# Backplane-Connector.net
KiCad netlist of a schematic drawn in Altium Designer
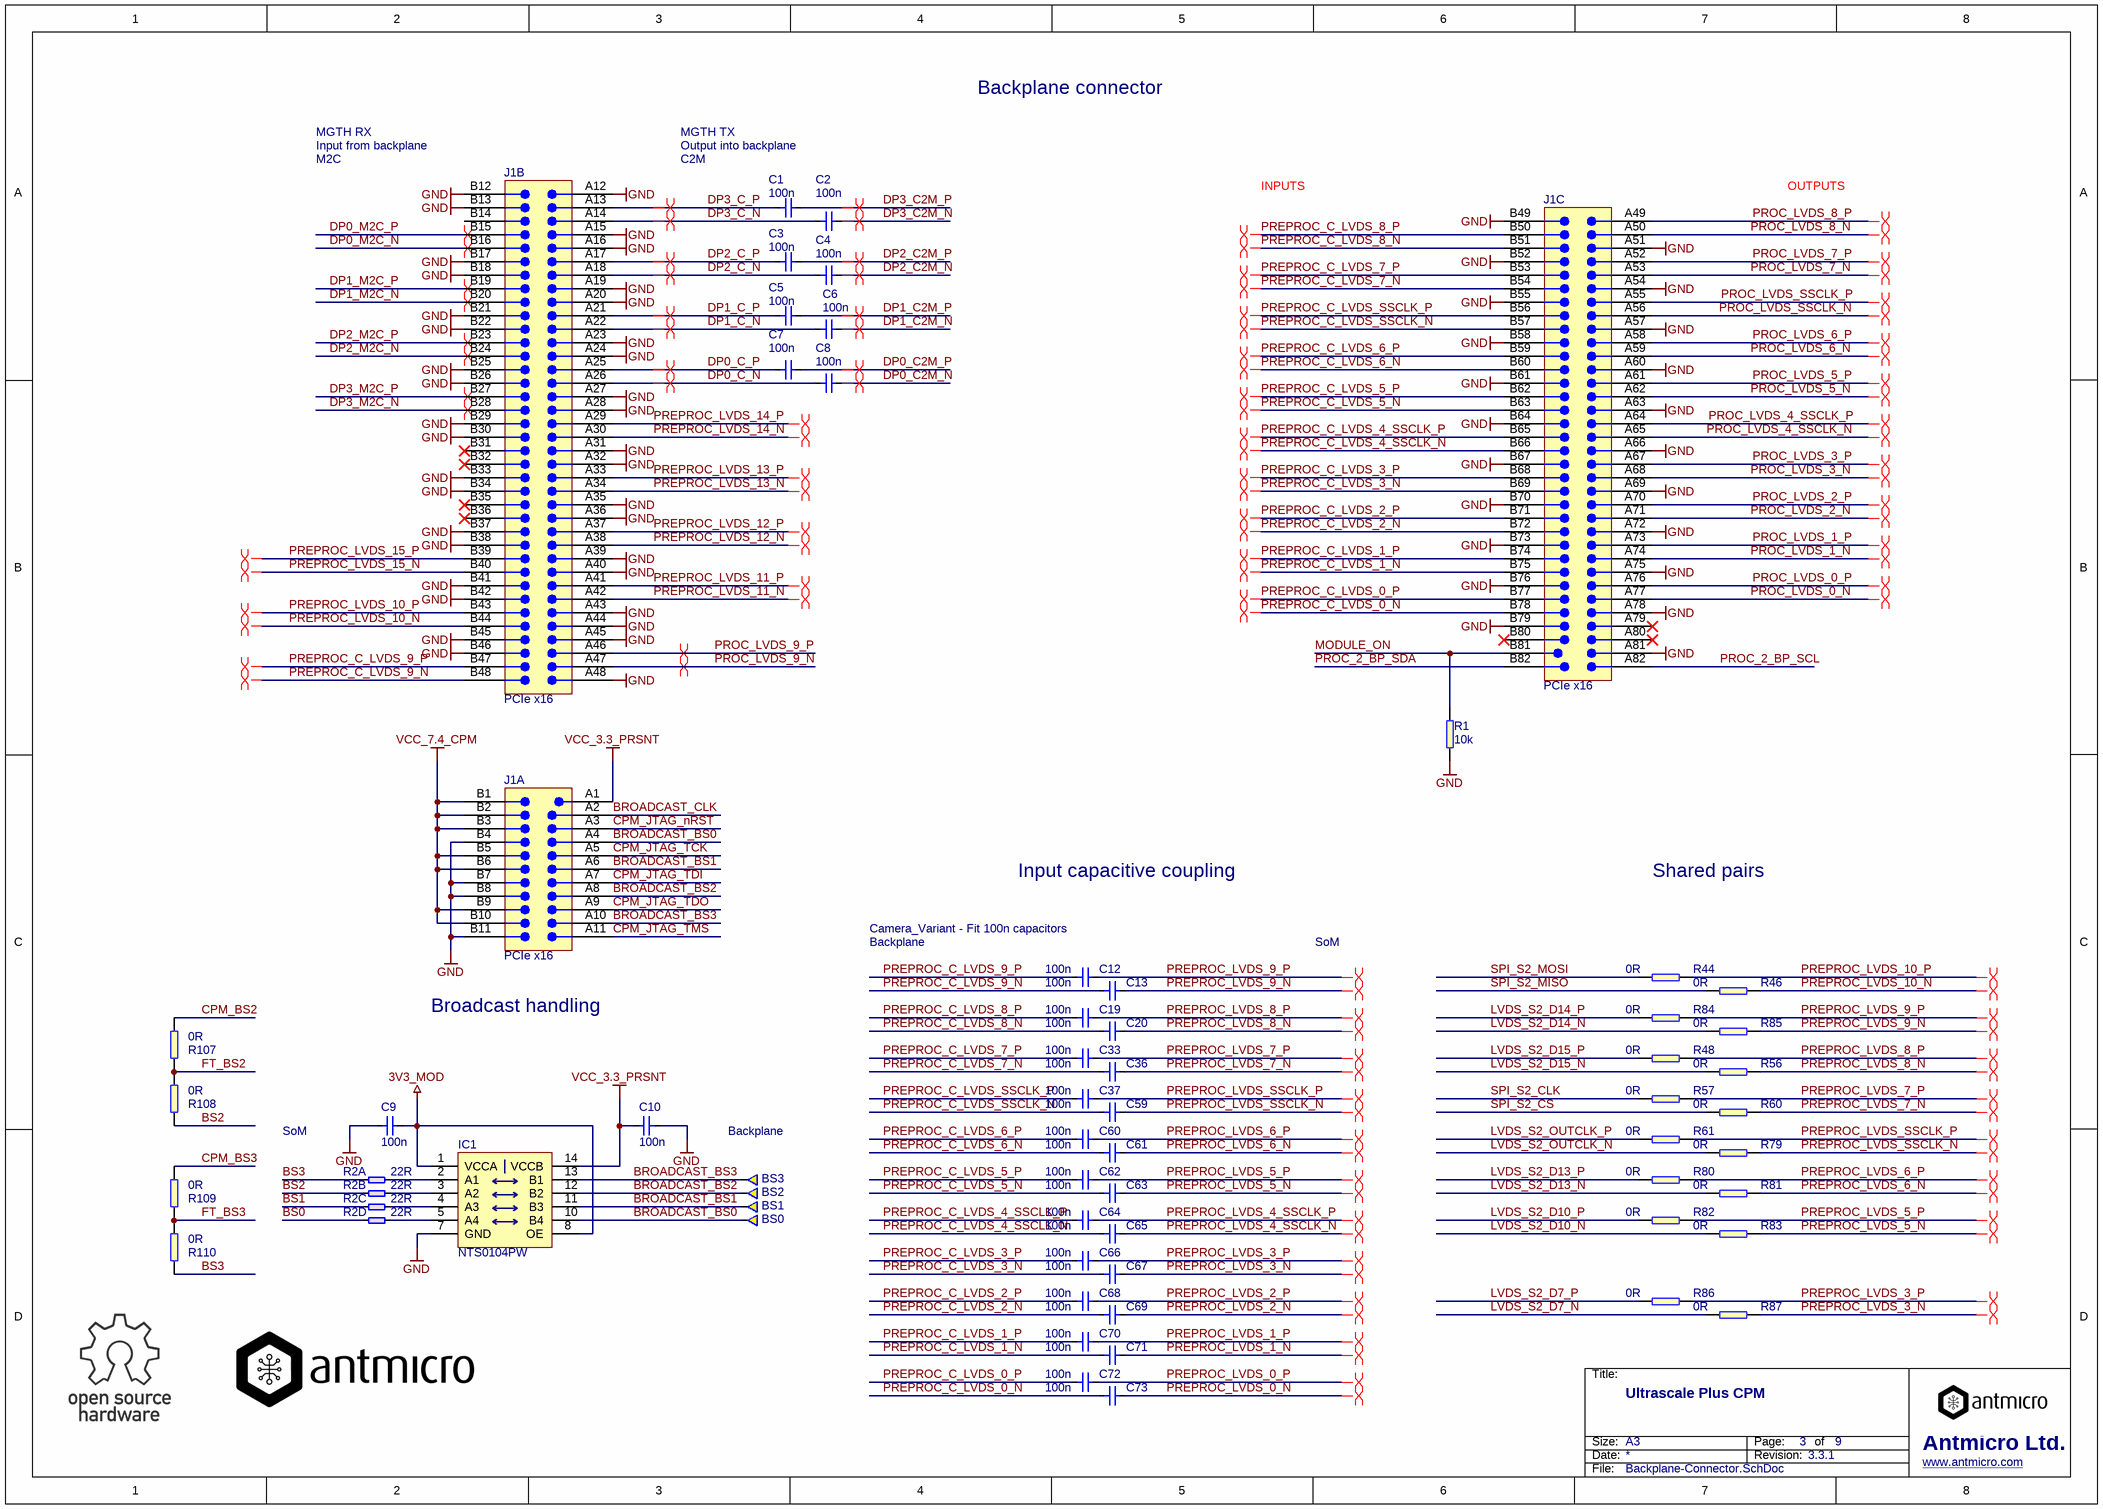
[diagram p0: Backplane-Connector.SchDoc]

(export (version "E")
  (design (tool "Eeschema 10.0.6"))
  (components
    (comp (ref "BS0")
      (value "*")
      (footprint "Testpad")
      (description "Testpad 2mm diameter")
      (fields (field (name "PART NUMBER") "Testpad"))
      (libsource (lib "US-Plus-CPM") (part "Testpad"))
    )
    (comp (ref "BS1")
      (value "*")
      (footprint "Testpad")
      (description "Testpad 2mm diameter")
      (fields (field (name "PART NUMBER") "Testpad"))
      (libsource (lib "US-Plus-CPM") (part "Testpad"))
    )
    (comp (ref "BS2")
      (value "*")
      (footprint "Testpad")
      (description "Testpad 2mm diameter")
      (fields (field (name "PART NUMBER") "Testpad"))
      (libsource (lib "US-Plus-CPM") (part "Testpad"))
    )
    (comp (ref "BS3")
      (value "*")
      (footprint "Testpad")
      (description "Testpad 2mm diameter")
      (fields (field (name "PART NUMBER") "Testpad"))
      (libsource (lib "US-Plus-CPM") (part "Testpad"))
    )
    (comp (ref "C1")
      (value "100n")
      (footprint "0402")
      (description "MLCC SMT Capacitor 100nF 0402")
      (fields (field (name "PART NUMBER") "C_100n_0402") (field (name "MANUFACTURER") "MULTICOMP"))
      (libsource (lib "US-Plus-CPM") (part "C"))
    )
    (comp (ref "C2")
      (value "100n")
      (footprint "0402")
      (description "MLCC SMT Capacitor 100nF 0402")
      (fields (field (name "PART NUMBER") "C_100n_0402") (field (name "MANUFACTURER") "MULTICOMP"))
      (libsource (lib "US-Plus-CPM") (part "C"))
    )
    (comp (ref "C3")
      (value "100n")
      (footprint "0402")
      (description "MLCC SMT Capacitor 100nF 0402")
      (fields (field (name "PART NUMBER") "C_100n_0402") (field (name "MANUFACTURER") "MULTICOMP"))
      (libsource (lib "US-Plus-CPM") (part "C"))
    )
    (comp (ref "C4")
      (value "100n")
      (footprint "0402")
      (description "MLCC SMT Capacitor 100nF 0402")
      (fields (field (name "PART NUMBER") "C_100n_0402") (field (name "MANUFACTURER") "MULTICOMP"))
      (libsource (lib "US-Plus-CPM") (part "C"))
    )
    (comp (ref "C5")
      (value "100n")
      (footprint "0402")
      (description "MLCC SMT Capacitor 100nF 0402")
      (fields (field (name "PART NUMBER") "C_100n_0402") (field (name "MANUFACTURER") "MULTICOMP"))
      (libsource (lib "US-Plus-CPM") (part "C"))
    )
    (comp (ref "C6")
      (value "100n")
      (footprint "0402")
      (description "MLCC SMT Capacitor 100nF 0402")
      (fields (field (name "PART NUMBER") "C_100n_0402") (field (name "MANUFACTURER") "MULTICOMP"))
      (libsource (lib "US-Plus-CPM") (part "C"))
    )
    (comp (ref "C7")
      (value "100n")
      (footprint "0402")
      (description "MLCC SMT Capacitor 100nF 0402")
      (fields (field (name "PART NUMBER") "C_100n_0402") (field (name "MANUFACTURER") "MULTICOMP"))
      (libsource (lib "US-Plus-CPM") (part "C"))
    )
    (comp (ref "C8")
      (value "100n")
      (footprint "0402")
      (description "MLCC SMT Capacitor 100nF 0402")
      (fields (field (name "PART NUMBER") "C_100n_0402") (field (name "MANUFACTURER") "MULTICOMP"))
      (libsource (lib "US-Plus-CPM") (part "C"))
    )
    (comp (ref "C9")
      (value "100n")
      (footprint "0402")
      (description "MLCC SMT Capacitor 100nF 0402")
      (fields (field (name "PART NUMBER") "C_100n_0402") (field (name "MANUFACTURER") "MULTICOMP"))
      (libsource (lib "US-Plus-CPM") (part "C"))
    )
    (comp (ref "C10")
      (value "100n")
      (footprint "0402")
      (description "MLCC SMT Capacitor 100nF 0402")
      (fields (field (name "PART NUMBER") "C_100n_0402") (field (name "MANUFACTURER") "MULTICOMP"))
      (libsource (lib "US-Plus-CPM") (part "C"))
    )
    (comp (ref "C12")
      (value "100n")
      (footprint "0402")
      (description "MLCC SMT Capacitor 100nF 0402")
      (fields (field (name "PART NUMBER") "C_100n_0402") (field (name "MANUFACTURER") "MULTICOMP"))
      (libsource (lib "US-Plus-CPM") (part "C"))
    )
    (comp (ref "C13")
      (value "100n")
      (footprint "0402")
      (description "MLCC SMT Capacitor 100nF 0402")
      (fields (field (name "PART NUMBER") "C_100n_0402") (field (name "MANUFACTURER") "MULTICOMP"))
      (libsource (lib "US-Plus-CPM") (part "C"))
    )
    (comp (ref "C19")
      (value "100n")
      (footprint "0402")
      (description "MLCC SMT Capacitor 100nF 0402")
      (fields (field (name "PART NUMBER") "C_100n_0402") (field (name "MANUFACTURER") "MULTICOMP"))
      (libsource (lib "US-Plus-CPM") (part "C"))
    )
    (comp (ref "C20")
      (value "100n")
      (footprint "0402")
      (description "MLCC SMT Capacitor 100nF 0402")
      (fields (field (name "PART NUMBER") "C_100n_0402") (field (name "MANUFACTURER") "MULTICOMP"))
      (libsource (lib "US-Plus-CPM") (part "C"))
    )
    (comp (ref "C33")
      (value "100n")
      (footprint "0402")
      (description "MLCC SMT Capacitor 100nF 0402")
      (fields (field (name "PART NUMBER") "C_100n_0402") (field (name "MANUFACTURER") "MULTICOMP"))
      (libsource (lib "US-Plus-CPM") (part "C"))
    )
    (comp (ref "C36")
      (value "100n")
      (footprint "0402")
      (description "MLCC SMT Capacitor 100nF 0402")
      (fields (field (name "PART NUMBER") "C_100n_0402") (field (name "MANUFACTURER") "MULTICOMP"))
      (libsource (lib "US-Plus-CPM") (part "C"))
    )
    (comp (ref "C37")
      (value "100n")
      (footprint "0402")
      (description "MLCC SMT Capacitor 100nF 0402")
      (fields (field (name "PART NUMBER") "C_100n_0402") (field (name "MANUFACTURER") "MULTICOMP"))
      (libsource (lib "US-Plus-CPM") (part "C"))
    )
    (comp (ref "C59")
      (value "100n")
      (footprint "0402")
      (description "MLCC SMT Capacitor 100nF 0402")
      (fields (field (name "PART NUMBER") "C_100n_0402") (field (name "MANUFACTURER") "MULTICOMP"))
      (libsource (lib "US-Plus-CPM") (part "C"))
    )
    (comp (ref "C60")
      (value "100n")
      (footprint "0402")
      (description "MLCC SMT Capacitor 100nF 0402")
      (fields (field (name "PART NUMBER") "C_100n_0402") (field (name "MANUFACTURER") "MULTICOMP"))
      (libsource (lib "US-Plus-CPM") (part "C"))
    )
    (comp (ref "C61")
      (value "100n")
      (footprint "0402")
      (description "MLCC SMT Capacitor 100nF 0402")
      (fields (field (name "PART NUMBER") "C_100n_0402") (field (name "MANUFACTURER") "MULTICOMP"))
      (libsource (lib "US-Plus-CPM") (part "C"))
    )
    (comp (ref "C62")
      (value "100n")
      (footprint "0402")
      (description "MLCC SMT Capacitor 100nF 0402")
      (fields (field (name "PART NUMBER") "C_100n_0402") (field (name "MANUFACTURER") "MULTICOMP"))
      (libsource (lib "US-Plus-CPM") (part "C"))
    )
    (comp (ref "C63")
      (value "100n")
      (footprint "0402")
      (description "MLCC SMT Capacitor 100nF 0402")
      (fields (field (name "PART NUMBER") "C_100n_0402") (field (name "MANUFACTURER") "MULTICOMP"))
      (libsource (lib "US-Plus-CPM") (part "C"))
    )
    (comp (ref "C64")
      (value "100n")
      (footprint "0402")
      (description "MLCC SMT Capacitor 100nF 0402")
      (fields (field (name "PART NUMBER") "C_100n_0402") (field (name "MANUFACTURER") "MULTICOMP"))
      (libsource (lib "US-Plus-CPM") (part "C"))
    )
    (comp (ref "C65")
      (value "100n")
      (footprint "0402")
      (description "MLCC SMT Capacitor 100nF 0402")
      (fields (field (name "PART NUMBER") "C_100n_0402") (field (name "MANUFACTURER") "MULTICOMP"))
      (libsource (lib "US-Plus-CPM") (part "C"))
    )
    (comp (ref "C66")
      (value "100n")
      (footprint "0402")
      (description "MLCC SMT Capacitor 100nF 0402")
      (fields (field (name "PART NUMBER") "C_100n_0402") (field (name "MANUFACTURER") "MULTICOMP"))
      (libsource (lib "US-Plus-CPM") (part "C"))
    )
    (comp (ref "C67")
      (value "100n")
      (footprint "0402")
      (description "MLCC SMT Capacitor 100nF 0402")
      (fields (field (name "PART NUMBER") "C_100n_0402") (field (name "MANUFACTURER") "MULTICOMP"))
      (libsource (lib "US-Plus-CPM") (part "C"))
    )
    (comp (ref "C68")
      (value "100n")
      (footprint "0402")
      (description "MLCC SMT Capacitor 100nF 0402")
      (fields (field (name "PART NUMBER") "C_100n_0402") (field (name "MANUFACTURER") "MULTICOMP"))
      (libsource (lib "US-Plus-CPM") (part "C"))
    )
    (comp (ref "C69")
      (value "100n")
      (footprint "0402")
      (description "MLCC SMT Capacitor 100nF 0402")
      (fields (field (name "PART NUMBER") "C_100n_0402") (field (name "MANUFACTURER") "MULTICOMP"))
      (libsource (lib "US-Plus-CPM") (part "C"))
    )
    (comp (ref "C70")
      (value "100n")
      (footprint "0402")
      (description "MLCC SMT Capacitor 100nF 0402")
      (fields (field (name "PART NUMBER") "C_100n_0402") (field (name "MANUFACTURER") "MULTICOMP"))
      (libsource (lib "US-Plus-CPM") (part "C"))
    )
    (comp (ref "C71")
      (value "100n")
      (footprint "0402")
      (description "MLCC SMT Capacitor 100nF 0402")
      (fields (field (name "PART NUMBER") "C_100n_0402") (field (name "MANUFACTURER") "MULTICOMP"))
      (libsource (lib "US-Plus-CPM") (part "C"))
    )
    (comp (ref "C72")
      (value "100n")
      (footprint "0402")
      (description "MLCC SMT Capacitor 100nF 0402")
      (fields (field (name "PART NUMBER") "C_100n_0402") (field (name "MANUFACTURER") "MULTICOMP"))
      (libsource (lib "US-Plus-CPM") (part "C"))
    )
    (comp (ref "C73")
      (value "100n")
      (footprint "0402")
      (description "MLCC SMT Capacitor 100nF 0402")
      (fields (field (name "PART NUMBER") "C_100n_0402") (field (name "MANUFACTURER") "MULTICOMP"))
      (libsource (lib "US-Plus-CPM") (part "C"))
    )
    (comp (ref "IC1")
      (value "NTS0104PW")
      (footprint "TSSOP-14")
      (description "4 bit voltage level translator")
      (fields (field (name "MANUFACTURER") "NXP"))
      (libsource (lib "US-Plus-CPM") (part "NTS0104"))
    )
    (comp (ref "J1")
      (value "PCIe x16")
      (footprint "PCIe_x16_card_edge")
      (description "PCI Express x16 164 2.36 mm")
      (fields (field (name "PART NUMBER") "10018783-10113TLF") (field (name "MPN") "generic"))
      (libsource (lib "US-Plus-CPM") (part "PCIe x16"))
    )
    (comp (ref "R1")
      (value "10k")
      (footprint "0603")
      (description "SMT Resistor 10k 0603")
      (fields (field (name "PART NUMBER") "R_10k_0603") (field (name "MANUFACTURER") "BOURNS"))
      (libsource (lib "US-Plus-CPM") (part "R"))
    )
    (comp (ref "R2")
      (value "22R")
      (footprint "BOURNS-CAY16-J4")
      (description "Bourns, 4 x 22R, CAY16")
      (fields (field (name "PART NUMBER") "CAY16-220J4LF") (field (name "MANUFACTURER") "BOURNS"))
      (libsource (lib "US-Plus-CPM") (part "Rnet4"))
    )
    (comp (ref "R44")
      (value "0R")
      (footprint "0402")
      (description "SMT Resistor 0402")
      (fields (field (name "PART NUMBER") "R_0R_0402") (field (name "MANUFACTURER") "MULTICOMP"))
      (libsource (lib "") (part "R_1"))
    )
    (comp (ref "R46")
      (value "0R")
      (footprint "0402")
      (description "SMT Resistor 0402")
      (fields (field (name "PART NUMBER") "R_0R_0402") (field (name "MANUFACTURER") "MULTICOMP"))
      (libsource (lib "") (part "R_1"))
    )
    (comp (ref "R48")
      (value "0R")
      (footprint "0402")
      (description "SMT Resistor 0402")
      (fields (field (name "PART NUMBER") "R_0R_0402") (field (name "MANUFACTURER") "MULTICOMP"))
      (libsource (lib "") (part "R_1"))
    )
    (comp (ref "R56")
      (value "0R")
      (footprint "0402")
      (description "SMT Resistor 0402")
      (fields (field (name "PART NUMBER") "R_0R_0402") (field (name "MANUFACTURER") "MULTICOMP"))
      (libsource (lib "") (part "R_1"))
    )
    (comp (ref "R57")
      (value "0R")
      (footprint "0402")
      (description "SMT Resistor 0402")
      (fields (field (name "PART NUMBER") "R_0R_0402") (field (name "MANUFACTURER") "MULTICOMP"))
      (libsource (lib "") (part "R_1"))
    )
    (comp (ref "R60")
      (value "0R")
      (footprint "0402")
      (description "SMT Resistor 0402")
      (fields (field (name "PART NUMBER") "R_0R_0402") (field (name "MANUFACTURER") "MULTICOMP"))
      (libsource (lib "") (part "R_1"))
    )
    (comp (ref "R61")
      (value "0R")
      (footprint "0402")
      (description "SMT Resistor 0402")
      (fields (field (name "PART NUMBER") "R_0R_0402") (field (name "MANUFACTURER") "MULTICOMP"))
      (libsource (lib "") (part "R_1"))
    )
    (comp (ref "R79")
      (value "0R")
      (footprint "0402")
      (description "SMT Resistor 0402")
      (fields (field (name "PART NUMBER") "R_0R_0402") (field (name "MANUFACTURER") "MULTICOMP"))
      (libsource (lib "") (part "R_1"))
    )
    (comp (ref "R80")
      (value "0R")
      (footprint "0402")
      (description "SMT Resistor 0402")
      (fields (field (name "PART NUMBER") "R_0R_0402") (field (name "MANUFACTURER") "MULTICOMP"))
      (libsource (lib "") (part "R_1"))
    )
    (comp (ref "R81")
      (value "0R")
      (footprint "0402")
      (description "SMT Resistor 0402")
      (fields (field (name "PART NUMBER") "R_0R_0402") (field (name "MANUFACTURER") "MULTICOMP"))
      (libsource (lib "") (part "R_1"))
    )
    (comp (ref "R82")
      (value "0R")
      (footprint "0402")
      (description "SMT Resistor 0402")
      (fields (field (name "PART NUMBER") "R_0R_0402") (field (name "MANUFACTURER") "MULTICOMP"))
      (libsource (lib "") (part "R_1"))
    )
    (comp (ref "R83")
      (value "0R")
      (footprint "0402")
      (description "SMT Resistor 0402")
      (fields (field (name "PART NUMBER") "R_0R_0402") (field (name "MANUFACTURER") "MULTICOMP"))
      (libsource (lib "") (part "R_1"))
    )
    (comp (ref "R84")
      (value "0R")
      (footprint "0402")
      (description "SMT Resistor 0402")
      (fields (field (name "PART NUMBER") "R_0R_0402") (field (name "MANUFACTURER") "MULTICOMP"))
      (libsource (lib "") (part "R_1"))
    )
    (comp (ref "R85")
      (value "0R")
      (footprint "0402")
      (description "SMT Resistor 0402")
      (fields (field (name "PART NUMBER") "R_0R_0402") (field (name "MANUFACTURER") "MULTICOMP"))
      (libsource (lib "") (part "R_1"))
    )
    (comp (ref "R86")
      (value "0R")
      (footprint "0402")
      (description "SMT Resistor 0402")
      (fields (field (name "PART NUMBER") "R_0R_0402") (field (name "MANUFACTURER") "MULTICOMP"))
      (libsource (lib "") (part "R_1"))
    )
    (comp (ref "R87")
      (value "0R")
      (footprint "0402")
      (description "SMT Resistor 0402")
      (fields (field (name "PART NUMBER") "R_0R_0402") (field (name "MANUFACTURER") "MULTICOMP"))
      (libsource (lib "") (part "R_1"))
    )
    (comp (ref "R107")
      (value "0R")
      (footprint "0402")
      (description "SMT Resistor 0402")
      (fields (field (name "MANUFACTURER") "MULTICOMP") (field (name "PART NUMBER") "R_0R_0402"))
      (libsource (lib "US-Plus-CPM") (part "R"))
    )
    (comp (ref "R108")
      (value "0R")
      (footprint "0402")
      (description "SMT Resistor 0402")
      (fields (field (name "MANUFACTURER") "MULTICOMP") (field (name "PART NUMBER") "R_0R_0402"))
      (libsource (lib "US-Plus-CPM") (part "R"))
    )
    (comp (ref "R109")
      (value "0R")
      (footprint "0402")
      (description "SMT Resistor 0402")
      (fields (field (name "MANUFACTURER") "MULTICOMP") (field (name "PART NUMBER") "R_0R_0402"))
      (libsource (lib "US-Plus-CPM") (part "R"))
    )
    (comp (ref "R110")
      (value "0R")
      (footprint "0402")
      (description "SMT Resistor 0402")
      (fields (field (name "MANUFACTURER") "MULTICOMP") (field (name "PART NUMBER") "R_0R_0402"))
      (libsource (lib "US-Plus-CPM") (part "R"))
    )
  )
  (nets
    (net (code "1") (name "/BROADCAST_BS0") (class "Default")
      (node (ref "BS0") (pin "1") (pintype "passive"))
      (node (ref "IC1") (pin "10") (pinfunction "B4_10") (pintype "passive"))
      (node (ref "J1") (pin "A4") (pinfunction "A4_A4") (pintype "passive"))
    )
    (net (code "2") (name "/BROADCAST_BS1") (class "Default")
      (node (ref "BS1") (pin "1") (pintype "passive"))
      (node (ref "IC1") (pin "11") (pinfunction "B3_11") (pintype "passive"))
      (node (ref "J1") (pin "A6") (pinfunction "A6_A6") (pintype "passive"))
    )
    (net (code "3") (name "/BROADCAST_BS2") (class "Default")
      (node (ref "BS2") (pin "1") (pintype "passive"))
      (node (ref "IC1") (pin "12") (pinfunction "B2_12") (pintype "passive"))
      (node (ref "J1") (pin "A8") (pinfunction "A8_A8") (pintype "passive"))
    )
    (net (code "4") (name "/BROADCAST_BS3") (class "Default")
      (node (ref "BS3") (pin "1") (pintype "passive"))
      (node (ref "IC1") (pin "13") (pinfunction "B1_13") (pintype "passive"))
      (node (ref "J1") (pin "A10") (pinfunction "A10_A10") (pintype "passive"))
    )
    (net (code "5") (name "/BROADCAST_CLK") (class "Default")
      (node (ref "J1") (pin "A2") (pinfunction "A2_A2") (pintype "passive"))
    )
    (net (code "6") (name "/BS0") (class "Default")
      (node (ref "R2") (pin "7") (pinfunction "7_7") (pintype "passive"))
    )
    (net (code "7") (name "/BS1") (class "Default")
      (node (ref "R2") (pin "5") (pinfunction "5_5") (pintype "passive"))
    )
    (net (code "8") (name "/BS2") (class "Default")
      (node (ref "R108") (pin "1") (pintype "passive"))
      (node (ref "R2") (pin "3") (pinfunction "3_3") (pintype "passive"))
    )
    (net (code "9") (name "/BS3") (class "Default")
      (node (ref "R110") (pin "1") (pintype "passive"))
      (node (ref "R2") (pin "1") (pinfunction "1_1") (pintype "passive"))
    )
    (net (code "10") (name "/CPM_BS2") (class "Default") (node (ref "R107") (pin "2") (pintype "passive")))
    (net (code "11") (name "/CPM_BS3") (class "Default") (node (ref "R109") (pin "2") (pintype "passive")))
    (net (code "12") (name "/CPM_JTAG_TCK") (class "Default")
      (node (ref "J1") (pin "A5") (pinfunction "A5_A5") (pintype "passive"))
    )
    (net (code "13") (name "/CPM_JTAG_TDI") (class "Default")
      (node (ref "J1") (pin "A7") (pinfunction "A7_A7") (pintype "passive"))
    )
    (net (code "14") (name "/CPM_JTAG_TDO") (class "Default")
      (node (ref "J1") (pin "A9") (pinfunction "A9_A9") (pintype "passive"))
    )
    (net (code "15") (name "/CPM_JTAG_TMS") (class "Default")
      (node (ref "J1") (pin "A11") (pinfunction "A11_A11") (pintype "passive"))
    )
    (net (code "16") (name "/CPM_JTAG_nRST") (class "Default")
      (node (ref "J1") (pin "A3") (pinfunction "A3_A3") (pintype "passive"))
    )
    (net (code "17") (name "/DP0_C2M_N") (class "Default")
      (node (ref "C8") (pin "2") (pinfunction "2_2") (pintype "passive"))
    )
    (net (code "18") (name "/DP0_C2M_P") (class "Default")
      (node (ref "C7") (pin "2") (pinfunction "2_2") (pintype "passive"))
    )
    (net (code "19") (name "/DP0_C_N") (class "Default")
      (node (ref "C8") (pin "1") (pinfunction "1_1") (pintype "passive"))
      (node (ref "J1") (pin "A26") (pinfunction "A26_A26") (pintype "passive"))
    )
    (net (code "20") (name "/DP0_C_P") (class "Default")
      (node (ref "C7") (pin "1") (pinfunction "1_1") (pintype "passive"))
      (node (ref "J1") (pin "A25") (pinfunction "A25_A25") (pintype "passive"))
    )
    (net (code "21") (name "/DP0_M2C_N") (class "Default")
      (node (ref "J1") (pin "B16") (pinfunction "B16_B16") (pintype "passive"))
    )
    (net (code "22") (name "/DP0_M2C_P") (class "Default")
      (node (ref "J1") (pin "B15") (pinfunction "B15_B15") (pintype "passive"))
    )
    (net (code "23") (name "/DP1_C2M_N") (class "Default")
      (node (ref "C6") (pin "2") (pinfunction "2_2") (pintype "passive"))
    )
    (net (code "24") (name "/DP1_C2M_P") (class "Default")
      (node (ref "C5") (pin "2") (pinfunction "2_2") (pintype "passive"))
    )
    (net (code "25") (name "/DP1_C_N") (class "Default")
      (node (ref "C6") (pin "1") (pinfunction "1_1") (pintype "passive"))
      (node (ref "J1") (pin "A22") (pinfunction "A22_A22") (pintype "passive"))
    )
    (net (code "26") (name "/DP1_C_P") (class "Default")
      (node (ref "C5") (pin "1") (pinfunction "1_1") (pintype "passive"))
      (node (ref "J1") (pin "A21") (pinfunction "A21_A21") (pintype "passive"))
    )
    (net (code "27") (name "/DP1_M2C_N") (class "Default")
      (node (ref "J1") (pin "B20") (pinfunction "B20_B20") (pintype "passive"))
    )
    (net (code "28") (name "/DP1_M2C_P") (class "Default")
      (node (ref "J1") (pin "B19") (pinfunction "B19_B19") (pintype "passive"))
    )
    (net (code "29") (name "/DP2_C2M_N") (class "Default")
      (node (ref "C4") (pin "2") (pinfunction "2_2") (pintype "passive"))
    )
    (net (code "30") (name "/DP2_C2M_P") (class "Default")
      (node (ref "C3") (pin "2") (pinfunction "2_2") (pintype "passive"))
    )
    (net (code "31") (name "/DP2_C_N") (class "Default")
      (node (ref "C4") (pin "1") (pinfunction "1_1") (pintype "passive"))
      (node (ref "J1") (pin "A18") (pinfunction "A18_A18") (pintype "passive"))
    )
    (net (code "32") (name "/DP2_C_P") (class "Default")
      (node (ref "C3") (pin "1") (pinfunction "1_1") (pintype "passive"))
      (node (ref "J1") (pin "A17") (pinfunction "A17_A17") (pintype "passive"))
    )
    (net (code "33") (name "/DP2_M2C_N") (class "Default")
      (node (ref "J1") (pin "B24") (pinfunction "B24_B24") (pintype "passive"))
    )
    (net (code "34") (name "/DP2_M2C_P") (class "Default")
      (node (ref "J1") (pin "B23") (pinfunction "B23_B23") (pintype "passive"))
    )
    (net (code "35") (name "/DP3_C2M_N") (class "Default")
      (node (ref "C2") (pin "2") (pinfunction "2_2") (pintype "passive"))
    )
    (net (code "36") (name "/DP3_C2M_P") (class "Default")
      (node (ref "C1") (pin "2") (pinfunction "2_2") (pintype "passive"))
    )
    (net (code "37") (name "/DP3_C_N") (class "Default")
      (node (ref "C2") (pin "1") (pinfunction "1_1") (pintype "passive"))
      (node (ref "J1") (pin "A14") (pinfunction "A14_A14") (pintype "passive"))
    )
    (net (code "38") (name "/DP3_C_P") (class "Default")
      (node (ref "C1") (pin "1") (pinfunction "1_1") (pintype "passive"))
      (node (ref "J1") (pin "A13") (pinfunction "A13_A13") (pintype "passive"))
    )
    (net (code "39") (name "/DP3_M2C_N") (class "Default")
      (node (ref "J1") (pin "B28") (pinfunction "B28_B28") (pintype "passive"))
    )
    (net (code "40") (name "/DP3_M2C_P") (class "Default")
      (node (ref "J1") (pin "B27") (pinfunction "B27_B27") (pintype "passive"))
    )
    (net (code "41") (name "/FT_BS2") (class "Default")
      (node (ref "R107") (pin "1") (pintype "passive"))
      (node (ref "R108") (pin "2") (pintype "passive"))
    )
    (net (code "42") (name "/FT_BS3") (class "Default")
      (node (ref "R109") (pin "1") (pintype "passive"))
      (node (ref "R110") (pin "2") (pintype "passive"))
    )
    (net (code "43") (name "/LVDS_S2_D7_N") (class "Default")
      (node (ref "R87") (pin "1") (pintype "passive"))
    )
    (net (code "44") (name "/LVDS_S2_D7_P") (class "Default")
      (node (ref "R86") (pin "1") (pintype "passive"))
    )
    (net (code "45") (name "/LVDS_S2_D10_N") (class "Default")
      (node (ref "R83") (pin "1") (pintype "passive"))
    )
    (net (code "46") (name "/LVDS_S2_D10_P") (class "Default")
      (node (ref "R82") (pin "1") (pintype "passive"))
    )
    (net (code "47") (name "/LVDS_S2_D13_N") (class "Default")
      (node (ref "R81") (pin "1") (pintype "passive"))
    )
    (net (code "48") (name "/LVDS_S2_D13_P") (class "Default")
      (node (ref "R80") (pin "1") (pintype "passive"))
    )
    (net (code "49") (name "/LVDS_S2_D14_N") (class "Default")
      (node (ref "R85") (pin "1") (pintype "passive"))
    )
    (net (code "50") (name "/LVDS_S2_D14_P") (class "Default")
      (node (ref "R84") (pin "1") (pintype "passive"))
    )
    (net (code "51") (name "/LVDS_S2_D15_N") (class "Default")
      (node (ref "R56") (pin "1") (pintype "passive"))
    )
    (net (code "52") (name "/LVDS_S2_D15_P") (class "Default")
      (node (ref "R48") (pin "1") (pintype "passive"))
    )
    (net (code "53") (name "/LVDS_S2_OUTCLK_N") (class "Default")
      (node (ref "R79") (pin "1") (pintype "passive"))
    )
    (net (code "54") (name "/LVDS_S2_OUTCLK_P") (class "Default")
      (node (ref "R61") (pin "1") (pintype "passive"))
    )
    (net (code "55") (name "/MODULE_ON") (class "Default")
      (node (ref "J1") (pin "B81") (pinfunction "B81_B81") (pintype "passive"))
      (node (ref "R1") (pin "2") (pintype "passive"))
    )
    (net (code "56") (name "/PREPROC_C_LVDS_0_N") (class "Default")
      (node (ref "C73") (pin "1") (pinfunction "1_1") (pintype "passive"))
      (node (ref "J1") (pin "B78") (pinfunction "B78_B78") (pintype "passive"))
    )
    (net (code "57") (name "/PREPROC_C_LVDS_0_P") (class "Default")
      (node (ref "C72") (pin "1") (pinfunction "1_1") (pintype "passive"))
      (node (ref "J1") (pin "B77") (pinfunction "B77_B77") (pintype "passive"))
    )
    (net (code "58") (name "/PREPROC_C_LVDS_1_N") (class "Default")
      (node (ref "C71") (pin "1") (pinfunction "1_1") (pintype "passive"))
      (node (ref "J1") (pin "B75") (pinfunction "B75_B75") (pintype "passive"))
    )
    (net (code "59") (name "/PREPROC_C_LVDS_1_P") (class "Default")
      (node (ref "C70") (pin "1") (pinfunction "1_1") (pintype "passive"))
      (node (ref "J1") (pin "B74") (pinfunction "B74_B74") (pintype "passive"))
    )
    (net (code "60") (name "/PREPROC_C_LVDS_2_N") (class "Default")
      (node (ref "C69") (pin "1") (pinfunction "1_1") (pintype "passive"))
      (node (ref "J1") (pin "B72") (pinfunction "B72_B72") (pintype "passive"))
    )
    (net (code "61") (name "/PREPROC_C_LVDS_2_P") (class "Default")
      (node (ref "C68") (pin "1") (pinfunction "1_1") (pintype "passive"))
      (node (ref "J1") (pin "B71") (pinfunction "B71_B71") (pintype "passive"))
    )
    (net (code "62") (name "/PREPROC_C_LVDS_3_N") (class "Default")
      (node (ref "C67") (pin "1") (pinfunction "1_1") (pintype "passive"))
      (node (ref "J1") (pin "B69") (pinfunction "B69_B69") (pintype "passive"))
    )
    (net (code "63") (name "/PREPROC_C_LVDS_3_P") (class "Default")
      (node (ref "C66") (pin "1") (pinfunction "1_1") (pintype "passive"))
      (node (ref "J1") (pin "B68") (pinfunction "B68_B68") (pintype "passive"))
    )
    (net (code "64") (name "/PREPROC_C_LVDS_4_SSCLK_N") (class "Default")
      (node (ref "C65") (pin "1") (pinfunction "1_1") (pintype "passive"))
      (node (ref "J1") (pin "B66") (pinfunction "B66_B66") (pintype "passive"))
    )
    (net (code "65") (name "/PREPROC_C_LVDS_4_SSCLK_P") (class "Default")
      (node (ref "C64") (pin "1") (pinfunction "1_1") (pintype "passive"))
      (node (ref "J1") (pin "B65") (pinfunction "B65_B65") (pintype "passive"))
    )
    (net (code "66") (name "/PREPROC_C_LVDS_5_N") (class "Default")
      (node (ref "C63") (pin "1") (pinfunction "1_1") (pintype "passive"))
      (node (ref "J1") (pin "B63") (pinfunction "B63_B63") (pintype "passive"))
    )
    (net (code "67") (name "/PREPROC_C_LVDS_5_P") (class "Default")
      (node (ref "C62") (pin "1") (pinfunction "1_1") (pintype "passive"))
      (node (ref "J1") (pin "B62") (pinfunction "B62_B62") (pintype "passive"))
    )
    (net (code "68") (name "/PREPROC_C_LVDS_6_N") (class "Default")
      (node (ref "C61") (pin "1") (pinfunction "1_1") (pintype "passive"))
      (node (ref "J1") (pin "B60") (pinfunction "B60_B60") (pintype "passive"))
    )
    (net (code "69") (name "/PREPROC_C_LVDS_6_P") (class "Default")
      (node (ref "C60") (pin "1") (pinfunction "1_1") (pintype "passive"))
      (node (ref "J1") (pin "B59") (pinfunction "B59_B59") (pintype "passive"))
    )
    (net (code "70") (name "/PREPROC_C_LVDS_7_N") (class "Default")
      (node (ref "C36") (pin "1") (pinfunction "1_1") (pintype "passive"))
      (node (ref "J1") (pin "B54") (pinfunction "B54_B54") (pintype "passive"))
    )
    (net (code "71") (name "/PREPROC_C_LVDS_7_P") (class "Default")
      (node (ref "C33") (pin "1") (pinfunction "1_1") (pintype "passive"))
      (node (ref "J1") (pin "B53") (pinfunction "B53_B53") (pintype "passive"))
    )
    (net (code "72") (name "/PREPROC_C_LVDS_8_N") (class "Default")
      (node (ref "C20") (pin "1") (pinfunction "1_1") (pintype "passive"))
      (node (ref "J1") (pin "B51") (pinfunction "B51_B51") (pintype "passive"))
    )
    (net (code "73") (name "/PREPROC_C_LVDS_8_P") (class "Default")
      (node (ref "C19") (pin "1") (pinfunction "1_1") (pintype "passive"))
      (node (ref "J1") (pin "B50") (pinfunction "B50_B50") (pintype "passive"))
    )
    (net (code "74") (name "/PREPROC_C_LVDS_9_N") (class "Default")
      (node (ref "C13") (pin "1") (pinfunction "1_1") (pintype "passive"))
      (node (ref "J1") (pin "B48") (pinfunction "B48_B48") (pintype "passive"))
    )
    (net (code "75") (name "/PREPROC_C_LVDS_9_P") (class "Default")
      (node (ref "C12") (pin "1") (pinfunction "1_1") (pintype "passive"))
      (node (ref "J1") (pin "B47") (pinfunction "B47_B47") (pintype "passive"))
    )
    (net (code "76") (name "/PREPROC_C_LVDS_SSCLK_N") (class "Default")
      (node (ref "C59") (pin "1") (pinfunction "1_1") (pintype "passive"))
      (node (ref "J1") (pin "B57") (pinfunction "B57_B57") (pintype "passive"))
    )
    (net (code "77") (name "/PREPROC_C_LVDS_SSCLK_P") (class "Default")
      (node (ref "C37") (pin "1") (pinfunction "1_1") (pintype "passive"))
      (node (ref "J1") (pin "B56") (pinfunction "B56_B56") (pintype "passive"))
    )
    (net (code "78") (name "/PREPROC_LVDS_0_N") (class "Default")
      (node (ref "C73") (pin "2") (pinfunction "2_2") (pintype "passive"))
    )
    (net (code "79") (name "/PREPROC_LVDS_0_P") (class "Default")
      (node (ref "C72") (pin "2") (pinfunction "2_2") (pintype "passive"))
    )
    (net (code "80") (name "/PREPROC_LVDS_1_N") (class "Default")
      (node (ref "C71") (pin "2") (pinfunction "2_2") (pintype "passive"))
    )
    (net (code "81") (name "/PREPROC_LVDS_1_P") (class "Default")
      (node (ref "C70") (pin "2") (pinfunction "2_2") (pintype "passive"))
    )
    (net (code "82") (name "/PREPROC_LVDS_2_N") (class "Default")
      (node (ref "C69") (pin "2") (pinfunction "2_2") (pintype "passive"))
    )
    (net (code "83") (name "/PREPROC_LVDS_2_P") (class "Default")
      (node (ref "C68") (pin "2") (pinfunction "2_2") (pintype "passive"))
    )
    (net (code "84") (name "/PREPROC_LVDS_3_N") (class "Default")
      (node (ref "C67") (pin "2") (pinfunction "2_2") (pintype "passive"))
      (node (ref "R87") (pin "2") (pintype "passive"))
    )
    (net (code "85") (name "/PREPROC_LVDS_3_P") (class "Default")
      (node (ref "C66") (pin "2") (pinfunction "2_2") (pintype "passive"))
      (node (ref "R86") (pin "2") (pintype "passive"))
    )
    (net (code "86") (name "/PREPROC_LVDS_4_SSCLK_N") (class "Default")
      (node (ref "C65") (pin "2") (pinfunction "2_2") (pintype "passive"))
    )
    (net (code "87") (name "/PREPROC_LVDS_4_SSCLK_P") (class "Default")
      (node (ref "C64") (pin "2") (pinfunction "2_2") (pintype "passive"))
    )
    (net (code "88") (name "/PREPROC_LVDS_5_N") (class "Default")
      (node (ref "C63") (pin "2") (pinfunction "2_2") (pintype "passive"))
      (node (ref "R83") (pin "2") (pintype "passive"))
    )
    (net (code "89") (name "/PREPROC_LVDS_5_P") (class "Default")
      (node (ref "C62") (pin "2") (pinfunction "2_2") (pintype "passive"))
      (node (ref "R82") (pin "2") (pintype "passive"))
    )
    (net (code "90") (name "/PREPROC_LVDS_6_N") (class "Default")
      (node (ref "C61") (pin "2") (pinfunction "2_2") (pintype "passive"))
      (node (ref "R81") (pin "2") (pintype "passive"))
    )
    (net (code "91") (name "/PREPROC_LVDS_6_P") (class "Default")
      (node (ref "C60") (pin "2") (pinfunction "2_2") (pintype "passive"))
      (node (ref "R80") (pin "2") (pintype "passive"))
    )
    (net (code "92") (name "/PREPROC_LVDS_7_N") (class "Default")
      (node (ref "C36") (pin "2") (pinfunction "2_2") (pintype "passive"))
      (node (ref "R60") (pin "2") (pintype "passive"))
    )
    (net (code "93") (name "/PREPROC_LVDS_7_P") (class "Default")
      (node (ref "C33") (pin "2") (pinfunction "2_2") (pintype "passive"))
      (node (ref "R57") (pin "2") (pintype "passive"))
    )
    (net (code "94") (name "/PREPROC_LVDS_8_N") (class "Default")
      (node (ref "C20") (pin "2") (pinfunction "2_2") (pintype "passive"))
      (node (ref "R56") (pin "2") (pintype "passive"))
    )
    (net (code "95") (name "/PREPROC_LVDS_8_P") (class "Default")
      (node (ref "C19") (pin "2") (pinfunction "2_2") (pintype "passive"))
      (node (ref "R48") (pin "2") (pintype "passive"))
    )
    (net (code "96") (name "/PREPROC_LVDS_9_N") (class "Default")
      (node (ref "C13") (pin "2") (pinfunction "2_2") (pintype "passive"))
      (node (ref "R85") (pin "2") (pintype "passive"))
    )
    (net (code "97") (name "/PREPROC_LVDS_9_P") (class "Default")
      (node (ref "C12") (pin "2") (pinfunction "2_2") (pintype "passive"))
      (node (ref "R84") (pin "2") (pintype "passive"))
    )
    (net (code "98") (name "/PREPROC_LVDS_10_N") (class "Default")
      (node (ref "J1") (pin "B44") (pinfunction "B44_B44") (pintype "passive"))
      (node (ref "R46") (pin "2") (pintype "passive"))
    )
    (net (code "99") (name "/PREPROC_LVDS_10_P") (class "Default")
      (node (ref "J1") (pin "B43") (pinfunction "B43_B43") (pintype "passive"))
      (node (ref "R44") (pin "2") (pintype "passive"))
    )
    (net (code "100") (name "/PREPROC_LVDS_11_N") (class "Default")
      (node (ref "J1") (pin "A42") (pinfunction "A42_A42") (pintype "passive"))
    )
    (net (code "101") (name "/PREPROC_LVDS_11_P") (class "Default")
      (node (ref "J1") (pin "A41") (pinfunction "A41_A41") (pintype "passive"))
    )
    (net (code "102") (name "/PREPROC_LVDS_12_N") (class "Default")
      (node (ref "J1") (pin "A38") (pinfunction "A38_A38") (pintype "passive"))
    )
    (net (code "103") (name "/PREPROC_LVDS_12_P") (class "Default")
      (node (ref "J1") (pin "A37") (pinfunction "A37_A37") (pintype "passive"))
    )
    (net (code "104") (name "/PREPROC_LVDS_13_N") (class "Default")
      (node (ref "J1") (pin "A34") (pinfunction "A34_A34") (pintype "passive"))
    )
    (net (code "105") (name "/PREPROC_LVDS_13_P") (class "Default")
      (node (ref "J1") (pin "A33") (pinfunction "A33_A33") (pintype "passive"))
    )
    (net (code "106") (name "/PREPROC_LVDS_14_N") (class "Default")
      (node (ref "J1") (pin "A30") (pinfunction "A30_A30") (pintype "passive"))
    )
    (net (code "107") (name "/PREPROC_LVDS_14_P") (class "Default")
      (node (ref "J1") (pin "A29") (pinfunction "A29_A29") (pintype "passive"))
    )
    (net (code "108") (name "/PREPROC_LVDS_15_N") (class "Default")
      (node (ref "J1") (pin "B40") (pinfunction "B40_B40") (pintype "passive"))
    )
    (net (code "109") (name "/PREPROC_LVDS_15_P") (class "Default")
      (node (ref "J1") (pin "B39") (pinfunction "B39_B39") (pintype "passive"))
    )
    (net (code "110") (name "/PREPROC_LVDS_SSCLK_N") (class "Default")
      (node (ref "C59") (pin "2") (pinfunction "2_2") (pintype "passive"))
      (node (ref "R79") (pin "2") (pintype "passive"))
    )
    (net (code "111") (name "/PREPROC_LVDS_SSCLK_P") (class "Default")
      (node (ref "C37") (pin "2") (pinfunction "2_2") (pintype "passive"))
      (node (ref "R61") (pin "2") (pintype "passive"))
    )
    (net (code "112") (name "/PROC_2_BP_SCL") (class "Default")
      (node (ref "J1") (pin "A82") (pinfunction "A82_A82") (pintype "passive"))
    )
    (net (code "113") (name "/PROC_2_BP_SDA") (class "Default")
      (node (ref "J1") (pin "B82") (pinfunction "B82_B82") (pintype "passive"))
    )
    (net (code "114") (name "/PROC_LVDS_0_N") (class "Default")
      (node (ref "J1") (pin "A77") (pinfunction "A77_A77") (pintype "passive"))
    )
    (net (code "115") (name "/PROC_LVDS_0_P") (class "Default")
      (node (ref "J1") (pin "A76") (pinfunction "A76_A76") (pintype "passive"))
    )
    (net (code "116") (name "/PROC_LVDS_1_N") (class "Default")
      (node (ref "J1") (pin "A74") (pinfunction "A74_A74") (pintype "passive"))
    )
    (net (code "117") (name "/PROC_LVDS_1_P") (class "Default")
      (node (ref "J1") (pin "A73") (pinfunction "A73_A73") (pintype "passive"))
    )
    (net (code "118") (name "/PROC_LVDS_2_N") (class "Default")
      (node (ref "J1") (pin "A71") (pinfunction "A71_A71") (pintype "passive"))
    )
    (net (code "119") (name "/PROC_LVDS_2_P") (class "Default")
      (node (ref "J1") (pin "A70") (pinfunction "A70_A70") (pintype "passive"))
    )
    (net (code "120") (name "/PROC_LVDS_3_N") (class "Default")
      (node (ref "J1") (pin "A68") (pinfunction "A68_A68") (pintype "passive"))
    )
    (net (code "121") (name "/PROC_LVDS_3_P") (class "Default")
      (node (ref "J1") (pin "A67") (pinfunction "A67_A67") (pintype "passive"))
    )
    (net (code "122") (name "/PROC_LVDS_4_SSCLK_N") (class "Default")
      (node (ref "J1") (pin "A65") (pinfunction "A65_A65") (pintype "passive"))
    )
    (net (code "123") (name "/PROC_LVDS_4_SSCLK_P") (class "Default")
      (node (ref "J1") (pin "A64") (pinfunction "A64_A64") (pintype "passive"))
    )
    (net (code "124") (name "/PROC_LVDS_5_N") (class "Default")
      (node (ref "J1") (pin "A62") (pinfunction "A62_A62") (pintype "passive"))
    )
    (net (code "125") (name "/PROC_LVDS_5_P") (class "Default")
      (node (ref "J1") (pin "A61") (pinfunction "A61_A61") (pintype "passive"))
    )
    (net (code "126") (name "/PROC_LVDS_6_N") (class "Default")
      (node (ref "J1") (pin "A59") (pinfunction "A59_A59") (pintype "passive"))
    )
    (net (code "127") (name "/PROC_LVDS_6_P") (class "Default")
      (node (ref "J1") (pin "A58") (pinfunction "A58_A58") (pintype "passive"))
    )
    (net (code "128") (name "/PROC_LVDS_7_N") (class "Default")
      (node (ref "J1") (pin "A53") (pinfunction "A53_A53") (pintype "passive"))
    )
    (net (code "129") (name "/PROC_LVDS_7_P") (class "Default")
      (node (ref "J1") (pin "A52") (pinfunction "A52_A52") (pintype "passive"))
    )
    (net (code "130") (name "/PROC_LVDS_8_N") (class "Default")
      (node (ref "J1") (pin "A50") (pinfunction "A50_A50") (pintype "passive"))
    )
    (net (code "131") (name "/PROC_LVDS_8_P") (class "Default")
      (node (ref "J1") (pin "A49") (pinfunction "A49_A49") (pintype "passive"))
    )
    (net (code "132") (name "/PROC_LVDS_9_N") (class "Default")
      (node (ref "J1") (pin "A47") (pinfunction "A47_A47") (pintype "passive"))
    )
    (net (code "133") (name "/PROC_LVDS_9_P") (class "Default")
      (node (ref "J1") (pin "A46") (pinfunction "A46_A46") (pintype "passive"))
    )
    (net (code "134") (name "/PROC_LVDS_SSCLK_N") (class "Default")
      (node (ref "J1") (pin "A56") (pinfunction "A56_A56") (pintype "passive"))
    )
    (net (code "135") (name "/PROC_LVDS_SSCLK_P") (class "Default")
      (node (ref "J1") (pin "A55") (pinfunction "A55_A55") (pintype "passive"))
    )
    (net (code "136") (name "/SPI_S2_CLK") (class "Default") (node (ref "R57") (pin "1") (pintype "passive")))
    (net (code "137") (name "/SPI_S2_CS") (class "Default") (node (ref "R60") (pin "1") (pintype "passive")))
    (net (code "138") (name "/SPI_S2_MISO") (class "Default")
      (node (ref "R46") (pin "1") (pintype "passive"))
    )
    (net (code "139") (name "/SPI_S2_MOSI") (class "Default")
      (node (ref "R44") (pin "1") (pintype "passive"))
    )
    (net (code "140") (name "3V3_MOD") (class "Default")
      (node (ref "C9") (pin "2") (pinfunction "2_2") (pintype "passive"))
      (node (ref "IC1") (pin "1") (pinfunction "VCCA_1") (pintype "passive"))
      (node (ref "IC1") (pin "8") (pinfunction "OE_8") (pintype "passive"))
    )
    (net (code "141") (name "GND") (class "Default")
      (node (ref "C10") (pin "1") (pinfunction "1_1") (pintype "passive"))
      (node (ref "C9") (pin "1") (pinfunction "1_1") (pintype "passive"))
      (node (ref "IC1") (pin "7") (pinfunction "GND_7") (pintype "passive"))
      (node (ref "J1") (pin "A12") (pinfunction "A12_A12") (pintype "passive"))
      (node (ref "J1") (pin "A15") (pinfunction "A15_A15") (pintype "passive"))
      (node (ref "J1") (pin "A16") (pinfunction "A16_A16") (pintype "passive"))
      (node (ref "J1") (pin "A19") (pinfunction "A19_A19") (pintype "passive"))
      (node (ref "J1") (pin "A20") (pinfunction "A20_A20") (pintype "passive"))
      (node (ref "J1") (pin "A23") (pinfunction "A23_A23") (pintype "passive"))
      (node (ref "J1") (pin "A24") (pinfunction "A24_A24") (pintype "passive"))
      (node (ref "J1") (pin "A27") (pinfunction "A27_A27") (pintype "passive"))
      (node (ref "J1") (pin "A28") (pinfunction "A28_A28") (pintype "passive"))
      (node (ref "J1") (pin "A31") (pinfunction "A31_A31") (pintype "passive"))
      (node (ref "J1") (pin "A32") (pinfunction "A32_A32") (pintype "passive"))
      (node (ref "J1") (pin "A35") (pinfunction "A35_A35") (pintype "passive"))
      (node (ref "J1") (pin "A36") (pinfunction "A36_A36") (pintype "passive"))
      (node (ref "J1") (pin "A39") (pinfunction "A39_A39") (pintype "passive"))
      (node (ref "J1") (pin "A40") (pinfunction "A40_A40") (pintype "passive"))
      (node (ref "J1") (pin "A43") (pinfunction "A43_A43") (pintype "passive"))
      (node (ref "J1") (pin "A44") (pinfunction "A44_A44") (pintype "passive"))
      (node (ref "J1") (pin "A45") (pinfunction "A45_A45") (pintype "passive"))
      (node (ref "J1") (pin "A48") (pinfunction "A48_A48") (pintype "passive"))
      (node (ref "J1") (pin "A51") (pinfunction "A51_A51") (pintype "passive"))
      (node (ref "J1") (pin "A54") (pinfunction "A54_A54") (pintype "passive"))
      (node (ref "J1") (pin "A57") (pinfunction "A57_A57") (pintype "passive"))
      (node (ref "J1") (pin "A60") (pinfunction "A60_A60") (pintype "passive"))
      (node (ref "J1") (pin "A63") (pinfunction "A63_A63") (pintype "passive"))
      (node (ref "J1") (pin "A66") (pinfunction "A66_A66") (pintype "passive"))
      (node (ref "J1") (pin "A69") (pinfunction "A69_A69") (pintype "passive"))
      (node (ref "J1") (pin "A72") (pinfunction "A72_A72") (pintype "passive"))
      (node (ref "J1") (pin "A75") (pinfunction "A75_A75") (pintype "passive"))
      (node (ref "J1") (pin "A78") (pinfunction "A78_A78") (pintype "passive"))
      (node (ref "J1") (pin "A81") (pinfunction "A81_A81") (pintype "passive"))
      (node (ref "J1") (pin "B11") (pinfunction "B11_B11") (pintype "passive"))
      (node (ref "J1") (pin "B12") (pinfunction "B12_B12") (pintype "passive"))
      (node (ref "J1") (pin "B13") (pinfunction "B13_B13") (pintype "passive"))
      (node (ref "J1") (pin "B17") (pinfunction "B17_B17") (pintype "passive"))
      (node (ref "J1") (pin "B18") (pinfunction "B18_B18") (pintype "passive"))
      (node (ref "J1") (pin "B21") (pinfunction "B21_B21") (pintype "passive"))
      (node (ref "J1") (pin "B22") (pinfunction "B22_B22") (pintype "passive"))
      (node (ref "J1") (pin "B25") (pinfunction "B25_B25") (pintype "passive"))
      (node (ref "J1") (pin "B26") (pinfunction "B26_B26") (pintype "passive"))
      (node (ref "J1") (pin "B29") (pinfunction "B29_B29") (pintype "passive"))
      (node (ref "J1") (pin "B30") (pinfunction "B30_B30") (pintype "passive"))
      (node (ref "J1") (pin "B33") (pinfunction "B33_B33") (pintype "passive"))
      (node (ref "J1") (pin "B34") (pinfunction "B34_B34") (pintype "passive"))
      (node (ref "J1") (pin "B37") (pinfunction "B37_B37") (pintype "passive"))
      (node (ref "J1") (pin "B38") (pinfunction "B38_B38") (pintype "passive"))
      (node (ref "J1") (pin "B4") (pinfunction "B4_B4") (pintype "passive"))
      (node (ref "J1") (pin "B41") (pinfunction "B41_B41") (pintype "passive"))
      (node (ref "J1") (pin "B42") (pinfunction "B42_B42") (pintype "passive"))
      (node (ref "J1") (pin "B45") (pinfunction "B45_B45") (pintype "passive"))
      (node (ref "J1") (pin "B46") (pinfunction "B46_B46") (pintype "passive"))
      (node (ref "J1") (pin "B49") (pinfunction "B49_B49") (pintype "passive"))
      (node (ref "J1") (pin "B52") (pinfunction "B52_B52") (pintype "passive"))
      (node (ref "J1") (pin "B55") (pinfunction "B55_B55") (pintype "passive"))
      (node (ref "J1") (pin "B58") (pinfunction "B58_B58") (pintype "passive"))
      (node (ref "J1") (pin "B61") (pinfunction "B61_B61") (pintype "passive"))
      (node (ref "J1") (pin "B64") (pinfunction "B64_B64") (pintype "passive"))
      (node (ref "J1") (pin "B67") (pinfunction "B67_B67") (pintype "passive"))
      (node (ref "J1") (pin "B7") (pinfunction "B7_B7") (pintype "passive"))
      (node (ref "J1") (pin "B70") (pinfunction "B70_B70") (pintype "passive"))
      (node (ref "J1") (pin "B73") (pinfunction "B73_B73") (pintype "passive"))
      (node (ref "J1") (pin "B76") (pinfunction "B76_B76") (pintype "passive"))
      (node (ref "J1") (pin "B79") (pinfunction "B79_B79") (pintype "passive"))
      (node (ref "J1") (pin "B8") (pinfunction "B8_B8") (pintype "passive"))
      (node (ref "R1") (pin "1") (pintype "passive"))
    )
    (net (code "142") (name "Net-(IC1-A1)") (class "Default")
      (node (ref "IC1") (pin "2") (pinfunction "A1_2") (pintype "passive"))
      (node (ref "R2") (pin "2") (pinfunction "2_2") (pintype "passive"))
    )
    (net (code "143") (name "Net-(IC1-A2)") (class "Default")
      (node (ref "IC1") (pin "3") (pinfunction "A2_3") (pintype "passive"))
      (node (ref "R2") (pin "4") (pinfunction "4_4") (pintype "passive"))
    )
    (net (code "144") (name "Net-(IC1-A3)") (class "Default")
      (node (ref "IC1") (pin "4") (pinfunction "A3_4") (pintype "passive"))
      (node (ref "R2") (pin "6") (pinfunction "6_6") (pintype "passive"))
    )
    (net (code "145") (name "Net-(IC1-A4)") (class "Default")
      (node (ref "IC1") (pin "5") (pinfunction "A4_5") (pintype "passive"))
      (node (ref "R2") (pin "8") (pinfunction "8_8") (pintype "passive"))
    )
    (net (code "146") (name "VCC_3.3_PRSNT") (class "Default")
      (node (ref "C10") (pin "2") (pinfunction "2_2") (pintype "passive"))
      (node (ref "IC1") (pin "14") (pinfunction "VCCB_14") (pintype "passive"))
      (node (ref "J1") (pin "A1") (pinfunction "A1_A1") (pintype "passive"))
    )
    (net (code "147") (name "VCC_7.4_CPM") (class "Default")
      (node (ref "J1") (pin "B1") (pinfunction "B1_B1") (pintype "passive"))
      (node (ref "J1") (pin "B10") (pinfunction "B10_B10") (pintype "passive"))
      (node (ref "J1") (pin "B2") (pinfunction "B2_B2") (pintype "passive"))
      (node (ref "J1") (pin "B3") (pinfunction "B3_B3") (pintype "passive"))
      (node (ref "J1") (pin "B5") (pinfunction "B5_B5") (pintype "passive"))
      (node (ref "J1") (pin "B6") (pinfunction "B6_B6") (pintype "passive"))
      (node (ref "J1") (pin "B9") (pinfunction "B9_B9") (pintype "passive"))
    )
    (net (code "148") (name "unconnected-(J1-PadA79)") (class "Default")
      (node (ref "J1") (pin "A79") (pinfunction "A79_A79") (pintype "passive+no_connect"))
    )
    (net (code "149") (name "unconnected-(J1-PadA80)") (class "Default")
      (node (ref "J1") (pin "A80") (pinfunction "A80_A80") (pintype "passive+no_connect"))
    )
    (net (code "150") (name "unconnected-(J1-PadB14)") (class "Default")
      (node (ref "J1") (pin "B14") (pinfunction "B14_B14") (pintype "passive"))
    )
    (net (code "151") (name "unconnected-(J1-PadB31)") (class "Default")
      (node (ref "J1") (pin "B31") (pinfunction "B31_B31") (pintype "passive+no_connect"))
    )
    (net (code "152") (name "unconnected-(J1-PadB32)") (class "Default")
      (node (ref "J1") (pin "B32") (pinfunction "B32_B32") (pintype "passive+no_connect"))
    )
    (net (code "153") (name "unconnected-(J1-PadB35)") (class "Default")
      (node (ref "J1") (pin "B35") (pinfunction "B35_B35") (pintype "passive+no_connect"))
    )
    (net (code "154") (name "unconnected-(J1-PadB36)") (class "Default")
      (node (ref "J1") (pin "B36") (pinfunction "B36_B36") (pintype "passive+no_connect"))
    )
    (net (code "155") (name "unconnected-(J1-PadB80)") (class "Default")
      (node (ref "J1") (pin "B80") (pinfunction "B80_B80") (pintype "passive+no_connect"))
    )
  )
)
